# valve_schematic.net
KiCad netlist of a schematic drawn in Altium Designer
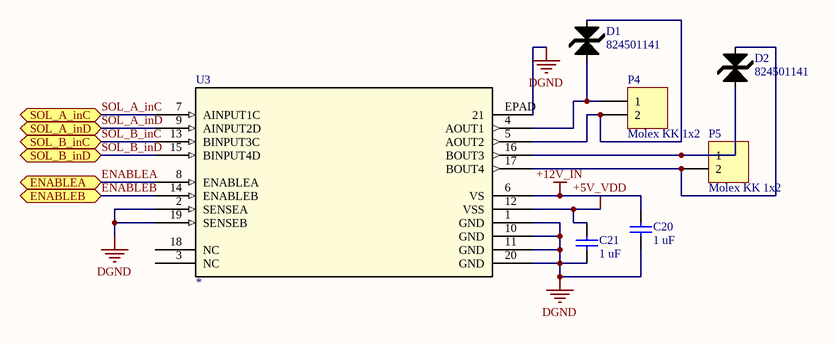
[diagram p0: valve_schematic.SchDoc]

(export (version "E")
  (design (tool "Eeschema 10.0.6"))
  (components
    (comp (ref "C20")
      (value "1 uF")
      (footprint "C0603")
      (description "0603 Capacitor")
      (libsource (lib "PARSEC") (part "C0603"))
    )
    (comp (ref "C21")
      (value "1 uF")
      (footprint "C0603")
      (description "0603 Capacitor")
      (libsource (lib "PARSEC") (part "C0603"))
    )
    (comp (ref "D1")
      (value "824501141")
      (footprint "DIODE-SMA")
      (description "TVS DIODE 14V 23.2V DO214AC")
      (libsource (lib "PARSEC") (part "824501141"))
    )
    (comp (ref "D2")
      (value "824501141")
      (footprint "DIODE-SMA")
      (description "TVS DIODE 14V 23.2V DO214AC")
      (libsource (lib "PARSEC") (part "824501141"))
    )
    (comp (ref "P4")
      (value "Molex KK 1x2")
      (footprint "Molex KK 2x1")
      (description "1x2 Molex KK Connector")
      (libsource (lib "PARSEC") (part "Molex KK 1x2"))
    )
    (comp (ref "P5")
      (value "Molex KK 1x2")
      (footprint "Molex KK 2x1")
      (description "1x2 Molex KK Connector")
      (libsource (lib "PARSEC") (part "Molex KK 1x2"))
    )
    (comp (ref "U3")
      (value "*")
      (footprint "PowerSO-20")
      (description "Imported")
      (fields (field (name "MANUFACTURER_PART_NUMBER") "L298P013TR"))
      (libsource (lib "PARSEC") (part "L298P013TR"))
    )
  )
  (nets
    (net (code "1") (name "+5V_VDD") (class "Default")
      (node (ref "C21") (pin "1") (pinfunction "1_1") (pintype "passive"))
      (node (ref "U3") (pin "12") (pinfunction "VSS_12") (pintype "power_in"))
    )
    (net (code "2") (name "+12V_IN") (class "Default")
      (node (ref "C20") (pin "1") (pinfunction "1_1") (pintype "passive"))
      (node (ref "U3") (pin "6") (pinfunction "VS_6") (pintype "power_in"))
    )
    (net (code "3") (name "/ENABLEA") (class "Default")
      (node (ref "U3") (pin "8") (pinfunction "ENABLEA_8") (pintype "input"))
    )
    (net (code "4") (name "/ENABLEB") (class "Default")
      (node (ref "U3") (pin "14") (pinfunction "ENABLEB_14") (pintype "input"))
    )
    (net (code "5") (name "/SOL_A_inC") (class "Default")
      (node (ref "U3") (pin "7") (pinfunction "AINPUT1C_7") (pintype "input"))
    )
    (net (code "6") (name "/SOL_A_inD") (class "Default")
      (node (ref "U3") (pin "9") (pinfunction "AINPUT2D_9") (pintype "input"))
    )
    (net (code "7") (name "/SOL_B_inC") (class "Default")
      (node (ref "U3") (pin "13") (pinfunction "BINPUT3C_13") (pintype "input"))
    )
    (net (code "8") (name "/SOL_B_inD") (class "Default")
      (node (ref "U3") (pin "15") (pinfunction "BINPUT4D_15") (pintype "input"))
    )
    (net (code "9") (name "DGND") (class "Default")
      (node (ref "C20") (pin "2") (pinfunction "2_2") (pintype "passive"))
      (node (ref "C21") (pin "2") (pinfunction "2_2") (pintype "passive"))
      (node (ref "U3") (pin "1") (pinfunction "GND_1") (pintype "passive"))
      (node (ref "U3") (pin "10") (pinfunction "GND_10") (pintype "passive"))
      (node (ref "U3") (pin "11") (pinfunction "GND_11") (pintype "passive"))
      (node (ref "U3") (pin "19") (pinfunction "SENSEB_19") (pintype "input"))
      (node (ref "U3") (pin "2") (pinfunction "SENSEA_2") (pintype "input"))
      (node (ref "U3") (pin "20") (pinfunction "GND_20") (pintype "passive"))
      (node (ref "U3") (pin "EPAD") (pinfunction "21_EPAD") (pintype "passive"))
    )
    (net (code "10") (name "Net-(U3-AOUT1)") (class "Default")
      (node (ref "D1") (pin "A") (pinfunction "A_A") (pintype "passive"))
      (node (ref "P4") (pin "1") (pinfunction "1_1") (pintype "passive"))
      (node (ref "U3") (pin "4") (pinfunction "AOUT1_4") (pintype "output"))
    )
    (net (code "11") (name "Net-(U3-AOUT2)") (class "Default")
      (node (ref "D1") (pin "K") (pinfunction "K_K") (pintype "passive"))
      (node (ref "P4") (pin "2") (pinfunction "2_2") (pintype "passive"))
      (node (ref "U3") (pin "5") (pinfunction "AOUT2_5") (pintype "output"))
    )
    (net (code "12") (name "Net-(U3-BOUT3)") (class "Default")
      (node (ref "D2") (pin "A") (pinfunction "A_A") (pintype "passive"))
      (node (ref "P5") (pin "1") (pinfunction "1_1") (pintype "passive"))
      (node (ref "U3") (pin "16") (pinfunction "BOUT3_16") (pintype "output"))
    )
    (net (code "13") (name "Net-(U3-BOUT4)") (class "Default")
      (node (ref "D2") (pin "K") (pinfunction "K_K") (pintype "passive"))
      (node (ref "P5") (pin "2") (pinfunction "2_2") (pintype "passive"))
      (node (ref "U3") (pin "17") (pinfunction "BOUT4_17") (pintype "output"))
    )
    (net (code "14") (name "unconnected-(U3-NC-Pad3)") (class "Default")
      (node (ref "U3") (pin "3") (pinfunction "NC_3") (pintype "passive"))
    )
    (net (code "15") (name "unconnected-(U3-NC-Pad18)") (class "Default")
      (node (ref "U3") (pin "18") (pinfunction "NC_18") (pintype "passive"))
    )
  )
)
